# Main.net
KiCad netlist of a schematic drawn in Altium Designer
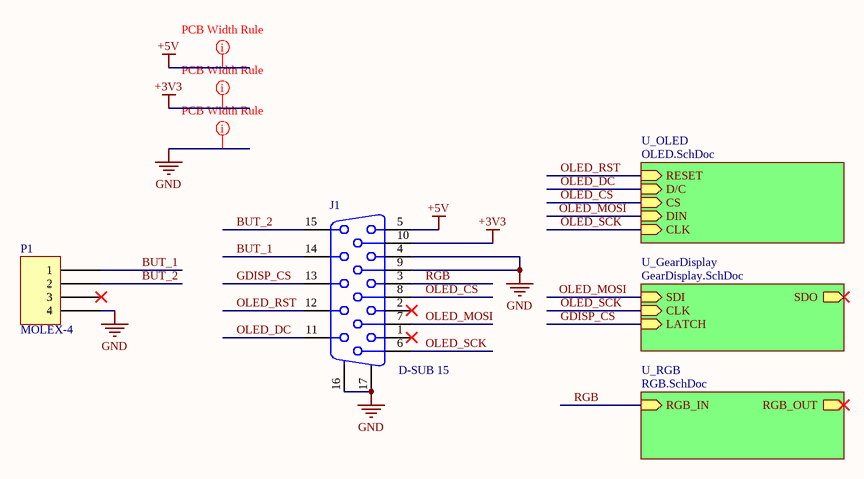
[diagram p0: Main.SchDoc]

(export (version "E")
  (design (tool "Eeschema 10.0.6"))
  (components
    (comp (ref "J1")
      (value "D-SUB 15")
      (footprint "Dsub-3H15")
      (description "Receptacle Assembly, 15-Pin, Sim Line Connector")
      (fields (field (name "MANUFACTURER") "TE Connectivity") (field (name "PUBLISHER") "Altium Limited"))
      (libsource (lib "Dashboard") (part "D-SUB 15"))
    )
    (comp (ref "P1")
      (value "MOLEX-4")
      (footprint "MOLEX_4_PIN")
      (description "4 pin socket")
      (fields (field (name "MANUFACTURER") "Molex"))
      (libsource (lib "Dashboard") (part "MOLEX-4"))
    )
  )
  (nets
    (net (code "1") (name "+3V3") (class "Default")
      (node (ref "J1") (pin "10") (pinfunction "10_10") (pintype "passive"))
    )
    (net (code "2") (name "+5V") (class "Default")
      (node (ref "J1") (pin "5") (pinfunction "5_5") (pintype "passive"))
    )
    (net (code "3") (name "/BUT_1") (class "Default")
      (node (ref "J1") (pin "14") (pinfunction "14_14") (pintype "passive"))
      (node (ref "P1") (pin "1") (pinfunction "1_1") (pintype "passive"))
    )
    (net (code "4") (name "/BUT_2") (class "Default")
      (node (ref "J1") (pin "15") (pinfunction "15_15") (pintype "passive"))
      (node (ref "P1") (pin "2") (pinfunction "2_2") (pintype "passive"))
    )
    (net (code "5") (name "/GDISP_CS") (class "Default")
      (node (ref "J1") (pin "13") (pinfunction "13_13") (pintype "passive"))
    )
    (net (code "6") (name "/OLED_CS") (class "Default")
      (node (ref "J1") (pin "8") (pinfunction "8_8") (pintype "passive"))
    )
    (net (code "7") (name "/OLED_DC") (class "Default")
      (node (ref "J1") (pin "11") (pinfunction "11_11") (pintype "passive"))
    )
    (net (code "8") (name "/OLED_MOSI") (class "Default")
      (node (ref "J1") (pin "7") (pinfunction "7_7") (pintype "passive"))
    )
    (net (code "9") (name "/OLED_RST") (class "Default")
      (node (ref "J1") (pin "12") (pinfunction "12_12") (pintype "passive"))
    )
    (net (code "10") (name "/OLED_SCK") (class "Default")
      (node (ref "J1") (pin "6") (pinfunction "6_6") (pintype "passive"))
    )
    (net (code "11") (name "/RGB") (class "Default")
      (node (ref "J1") (pin "3") (pinfunction "3_3") (pintype "passive"))
    )
    (net (code "14") (name "GND") (class "Default")
      (node (ref "J1") (pin "16") (pinfunction "MH1_16") (pintype "passive"))
      (node (ref "J1") (pin "17") (pinfunction "MH2_17") (pintype "passive"))
      (node (ref "J1") (pin "4") (pinfunction "4_4") (pintype "passive"))
      (node (ref "J1") (pin "9") (pinfunction "9_9") (pintype "passive"))
      (node (ref "P1") (pin "4") (pinfunction "4_4") (pintype "passive"))
    )
    (net (code "15") (name "unconnected-(J1-Pad1)") (class "Default")
      (node (ref "J1") (pin "1") (pinfunction "1_1") (pintype "passive+no_connect"))
    )
    (net (code "16") (name "unconnected-(J1-Pad2)") (class "Default")
      (node (ref "J1") (pin "2") (pinfunction "2_2") (pintype "passive+no_connect"))
    )
    (net (code "17") (name "unconnected-(P1-Pad3)") (class "Default")
      (node (ref "P1") (pin "3") (pinfunction "3_3") (pintype "passive+no_connect"))
    )
  )
)
